# CPU.net
KiCad netlist of a schematic drawn in Altium Designer
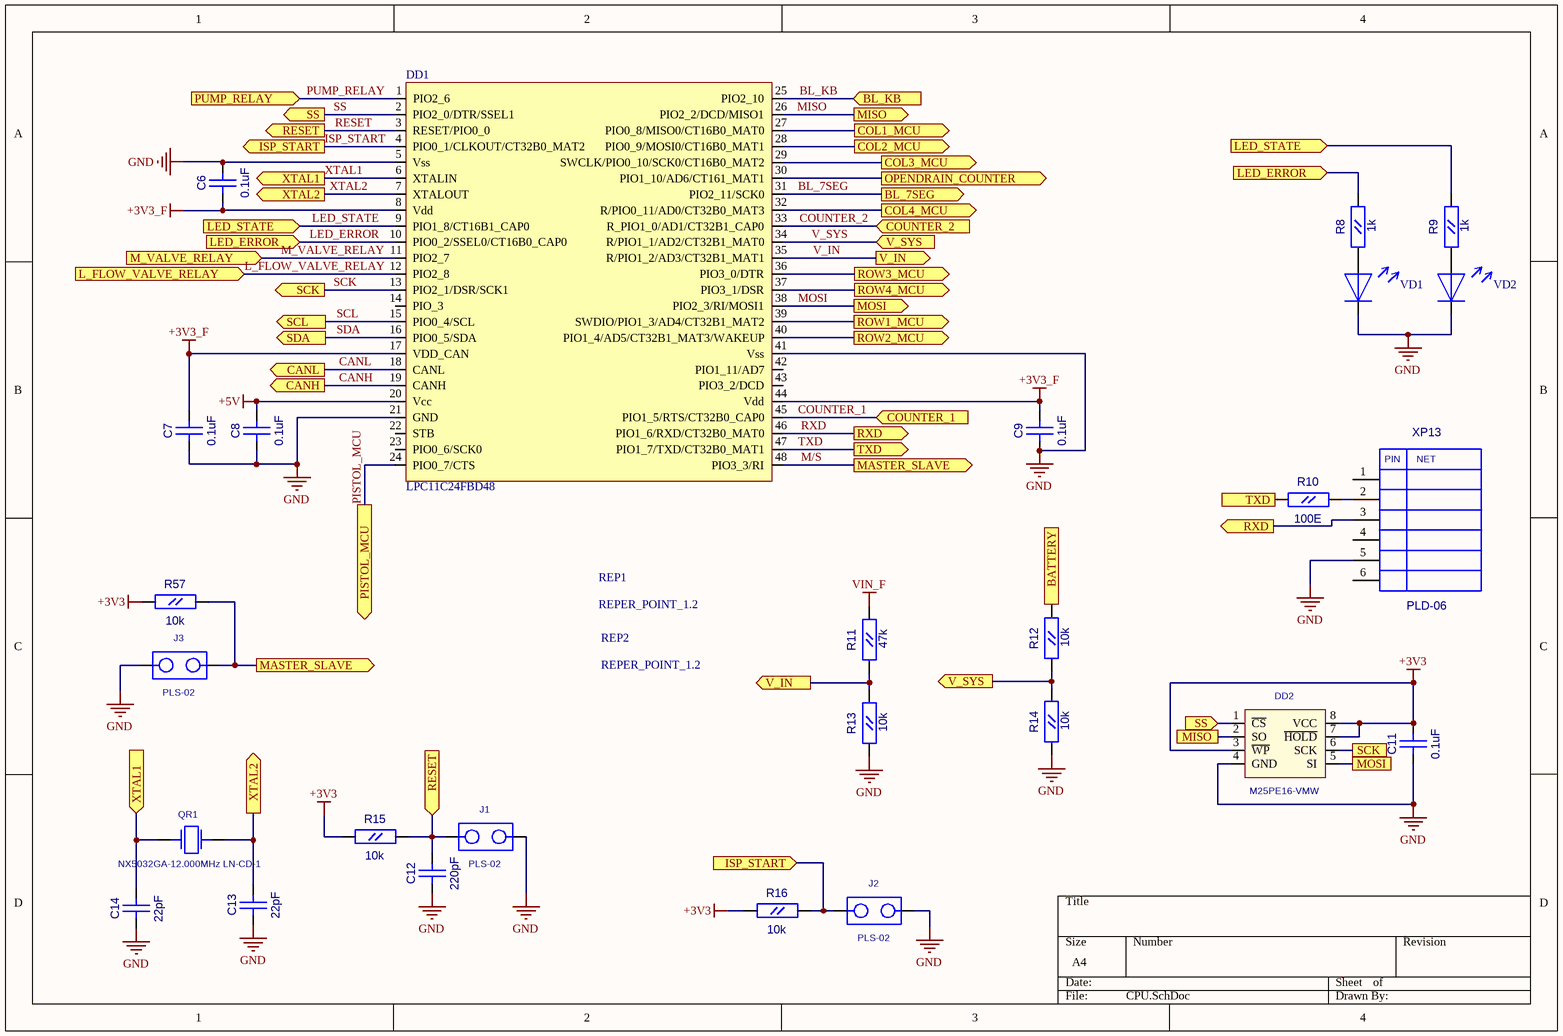
[diagram p0: CPU.SchDoc]

(export (version "E")
  (design (tool "Eeschema 10.0.6"))
  (components
    (comp (ref "C6")
      (value "0.1uF")
      (footprint "CC0603")
      (description "CC0603")
      (libsource (lib "gprs_modem_2") (part "CC0603"))
    )
    (comp (ref "C7")
      (value "0.1uF")
      (footprint "CC0603")
      (description "CC0603")
      (libsource (lib "gprs_modem_2") (part "CC0603"))
    )
    (comp (ref "C8")
      (value "0.1uF")
      (footprint "CC0603")
      (description "CC0603")
      (libsource (lib "gprs_modem_2") (part "CC0603"))
    )
    (comp (ref "C9")
      (value "0.1uF")
      (footprint "CC0603")
      (description "CC0603")
      (libsource (lib "gprs_modem_2") (part "CC0603"))
    )
    (comp (ref "C11")
      (value "0.1uF")
      (footprint "CC0603")
      (description "CC0603")
      (libsource (lib "gprs_modem_2") (part "CC0603"))
    )
    (comp (ref "C12")
      (value "220pF")
      (footprint "CC0603")
      (description "CC0603")
      (libsource (lib "gprs_modem_2") (part "CC0603"))
    )
    (comp (ref "C13")
      (value "22pF")
      (footprint "CC0603")
      (description "CC0603")
      (libsource (lib "gprs_modem_2") (part "CC0603"))
    )
    (comp (ref "C14")
      (value "22pF")
      (footprint "CC0603")
      (description "CC0603")
      (libsource (lib "gprs_modem_2") (part "CC0603"))
    )
    (comp (ref "DD1")
      (value "LPC11C24FBD48")
      (footprint "LQFP48")
      (libsource (lib "gprs_modem_2") (part "LPC11C24FBD48"))
    )
    (comp (ref "DD2")
      (value "M25PE16-VMW")
      (footprint "EIAJ_SO8")
      (description "S25FL016A0LMFI01")
      (libsource (lib "gprs_modem_2") (part "S25FL016A0LMFI01"))
    )
    (comp (ref "J1") (value "PLS-02") (footprint "PLS-02") (libsource (lib "gprs_modem_2") (part "PLS-02")))
    (comp (ref "J2") (value "PLS-02") (footprint "PLS-02") (libsource (lib "gprs_modem_2") (part "PLS-02")))
    (comp (ref "J3") (value "PLS-02") (footprint "PLS-02") (libsource (lib "gprs_modem_2") (part "PLS-02")))
    (comp (ref "QR1")
      (value "NX5032GA-12.000MHz LN-CD-1")
      (footprint "AC5032_2")
      (description "AC5032/2")
      (libsource (lib "gprs_modem_2") (part "AC5032_2"))
    )
    (comp (ref "R8")
      (value "1k")
      (footprint "RC0603")
      (description "RC0603")
      (libsource (lib "gprs_modem_2") (part "RC0603"))
    )
    (comp (ref "R9")
      (value "1k")
      (footprint "RC0603")
      (description "RC0603")
      (libsource (lib "gprs_modem_2") (part "RC0603"))
    )
    (comp (ref "R10")
      (value "100E")
      (footprint "RC0603")
      (description "RC0603")
      (libsource (lib "gprs_modem_2") (part "RC0603"))
    )
    (comp (ref "R11")
      (value "47k")
      (footprint "RC0603")
      (description "RC0603")
      (libsource (lib "gprs_modem_2") (part "RC0603"))
    )
    (comp (ref "R12")
      (value "10k")
      (footprint "RC0603")
      (description "RC0603")
      (libsource (lib "gprs_modem_2") (part "RC0603"))
    )
    (comp (ref "R13")
      (value "10k")
      (footprint "RC0603")
      (description "RC0603")
      (libsource (lib "gprs_modem_2") (part "RC0603"))
    )
    (comp (ref "R14")
      (value "10k")
      (footprint "RC0603")
      (description "RC0603")
      (libsource (lib "gprs_modem_2") (part "RC0603"))
    )
    (comp (ref "R15")
      (value "10k")
      (footprint "RC0603")
      (description "RC0603")
      (libsource (lib "gprs_modem_2") (part "RC0603"))
    )
    (comp (ref "R16")
      (value "10k")
      (footprint "RC0603")
      (description "RC0603")
      (libsource (lib "gprs_modem_2") (part "RC0603"))
    )
    (comp (ref "R57")
      (value "10k")
      (footprint "RC0603")
      (description "RC0603")
      (libsource (lib "gprs_modem_2") (part "RC0603"))
    )
    (comp (ref "REP1")
      (value "REPER_POINT_1.2")
      (footprint "REPER1.2")
      (description "REPER1.2")
      (libsource (lib "gprs_modem_2") (part "REPER1.2"))
    )
    (comp (ref "REP2")
      (value "REPER_POINT_1.2")
      (footprint "REPER1.2")
      (description "REPER1.2")
      (libsource (lib "gprs_modem_2") (part "REPER1.2"))
    )
    (comp (ref "VD1")
      (value "LED_0805")
      (footprint "LED0805")
      (libsource (lib "gprs_modem_2") (part "LED_0805"))
    )
    (comp (ref "VD2")
      (value "LED_0805")
      (footprint "LED0805")
      (libsource (lib "gprs_modem_2") (part "LED_0805"))
    )
    (comp (ref "XP13")
      (value "PLD-06")
      (footprint "PIN6")
      (description "PLD06")
      (libsource (lib "gprs_modem_2") (part "PLD-06"))
    )
  )
  (nets
    (net (code "1") (name "+3V3") (class "Default")
      (node (ref "C11") (pin "2") (pinfunction "B_2") (pintype "passive"))
      (node (ref "DD2") (pin "3") (pinfunction "~{WP}_3") (pintype "passive"))
      (node (ref "DD2") (pin "7") (pinfunction "~{HOLD}_7") (pintype "passive"))
      (node (ref "DD2") (pin "8") (pinfunction "VCC_8") (pintype "passive"))
      (node (ref "R15") (pin "1") (pinfunction "A_1") (pintype "passive"))
      (node (ref "R16") (pin "1") (pinfunction "A_1") (pintype "passive"))
      (node (ref "R57") (pin "1") (pinfunction "A_1") (pintype "passive"))
    )
    (net (code "2") (name "+3V3_F") (class "Default")
      (node (ref "C6") (pin "1") (pinfunction "A_1") (pintype "passive"))
      (node (ref "C7") (pin "2") (pinfunction "B_2") (pintype "passive"))
      (node (ref "C9") (pin "2") (pinfunction "B_2") (pintype "passive"))
      (node (ref "DD1") (pin "17") (pinfunction "VDD_CAN_17") (pintype "passive"))
      (node (ref "DD1") (pin "44") (pinfunction "Vdd_44") (pintype "passive"))
      (node (ref "DD1") (pin "8") (pinfunction "Vdd_8") (pintype "passive"))
    )
    (net (code "3") (name "+5V") (class "Default")
      (node (ref "C8") (pin "2") (pinfunction "B_2") (pintype "passive"))
      (node (ref "DD1") (pin "20") (pinfunction "Vcc_20") (pintype "passive"))
    )
    (net (code "4") (name "/BATTERY") (class "Default")
      (node (ref "R12") (pin "2") (pinfunction "B_2") (pintype "passive"))
    )
    (net (code "5") (name "/BL_7SEG") (class "Default")
      (node (ref "DD1") (pin "31") (pinfunction "PIO2_11/SCK0_31") (pintype "passive"))
    )
    (net (code "6") (name "/BL_KB") (class "Default")
      (node (ref "DD1") (pin "25") (pinfunction "PIO2_10_25") (pintype "passive"))
    )
    (net (code "7") (name "/CANH") (class "Default")
      (node (ref "DD1") (pin "19") (pinfunction "CANH_19") (pintype "passive"))
    )
    (net (code "8") (name "/CANL") (class "Default")
      (node (ref "DD1") (pin "18") (pinfunction "CANL_18") (pintype "passive"))
    )
    (net (code "9") (name "/COL1_MCU") (class "Default")
      (node (ref "DD1") (pin "27") (pinfunction "PIO0_8/MISO0/CT16B0_MAT0_27") (pintype "passive"))
    )
    (net (code "10") (name "/COL2_MCU") (class "Default")
      (node (ref "DD1") (pin "28") (pinfunction "PIO0_9/MOSI0/CT16B0_MAT1_28") (pintype "passive"))
    )
    (net (code "11") (name "/COL3_MCU") (class "Default")
      (node (ref "DD1") (pin "29") (pinfunction "SWCLK/PIO0_10/SCK0/CT16B0_MAT2_29") (pintype "passive"))
    )
    (net (code "12") (name "/COL4_MCU") (class "Default")
      (node (ref "DD1") (pin "32") (pinfunction "R/PIO0_11/AD0/CT32B0_MAT3_32") (pintype "passive"))
    )
    (net (code "13") (name "/COUNTER_1") (class "Default")
      (node (ref "DD1") (pin "45") (pinfunction "PIO1_5/RTS/CT32B0_CAP0_45") (pintype "passive"))
    )
    (net (code "14") (name "/COUNTER_2") (class "Default")
      (node (ref "DD1") (pin "33") (pinfunction "R_PIO1_0/AD1/CT32B1_CAP0_33") (pintype "passive"))
    )
    (net (code "15") (name "/ISP_START") (class "Default")
      (node (ref "DD1") (pin "4") (pinfunction "PIO0_1/CLKOUT/CT32B0_MAT2_4") (pintype "passive"))
      (node (ref "J2") (pin "1") (pintype "passive"))
      (node (ref "R16") (pin "2") (pinfunction "B_2") (pintype "passive"))
    )
    (net (code "16") (name "/LED_ERROR") (class "Default")
      (node (ref "DD1") (pin "10") (pinfunction "PIO0_2/SSEL0/CT16B0_CAP0_10") (pintype "passive"))
      (node (ref "R8") (pin "2") (pinfunction "B_2") (pintype "passive"))
    )
    (net (code "17") (name "/LED_STATE") (class "Default")
      (node (ref "DD1") (pin "9") (pinfunction "PIO1_8/CT16B1_CAP0_9") (pintype "passive"))
      (node (ref "R9") (pin "2") (pinfunction "B_2") (pintype "passive"))
    )
    (net (code "18") (name "/L_FLOW_VALVE_RELAY") (class "Default")
      (node (ref "DD1") (pin "12") (pinfunction "PIO2_8_12") (pintype "passive"))
    )
    (net (code "19") (name "/MISO") (class "Default")
      (node (ref "DD1") (pin "26") (pinfunction "PIO2_2/DCD/MISO1_26") (pintype "passive"))
      (node (ref "DD2") (pin "2") (pinfunction "SO_2") (pintype "passive"))
    )
    (net (code "20") (name "/MOSI") (class "Default")
      (node (ref "DD1") (pin "38") (pinfunction "PIO2_3/RI/MOSI1_38") (pintype "passive"))
      (node (ref "DD2") (pin "5") (pinfunction "SI_5") (pintype "passive"))
    )
    (net (code "21") (name "/M_VALVE_RELAY") (class "Default")
      (node (ref "DD1") (pin "11") (pinfunction "PIO2_7_11") (pintype "passive"))
    )
    (net (code "22") (name "/M{slash}S") (class "Default")
      (node (ref "DD1") (pin "48") (pinfunction "PIO3_3/RI_48") (pintype "passive"))
      (node (ref "J3") (pin "2") (pintype "passive"))
      (node (ref "R57") (pin "2") (pinfunction "B_2") (pintype "passive"))
    )
    (net (code "23") (name "/OPENDRAIN_COUNTER") (class "Default")
      (node (ref "DD1") (pin "30") (pinfunction "PIO1_10/AD6/CT161_MAT1_30") (pintype "passive"))
    )
    (net (code "24") (name "/PISTOL_MCU") (class "Default")
      (node (ref "DD1") (pin "24") (pinfunction "PIO0_7/CTS_24") (pintype "passive"))
    )
    (net (code "25") (name "/PUMP_RELAY") (class "Default")
      (node (ref "DD1") (pin "1") (pinfunction "PIO2_6_1") (pintype "passive"))
    )
    (net (code "26") (name "/RESET") (class "Default")
      (node (ref "C12") (pin "2") (pinfunction "B_2") (pintype "passive"))
      (node (ref "DD1") (pin "3") (pinfunction "RESET/PIO0_0_3") (pintype "passive"))
      (node (ref "J1") (pin "1") (pintype "passive"))
      (node (ref "R15") (pin "2") (pinfunction "B_2") (pintype "passive"))
    )
    (net (code "27") (name "/ROW1_MCU") (class "Default")
      (node (ref "DD1") (pin "39") (pinfunction "SWDIO/PIO1_3/AD4/CT32B1_MAT2_39") (pintype "passive"))
    )
    (net (code "28") (name "/ROW2_MCU") (class "Default")
      (node (ref "DD1") (pin "40") (pinfunction "PIO1_4/AD5/CT32B1_MAT3/WAKEUP_40") (pintype "passive"))
    )
    (net (code "29") (name "/ROW3_MCU") (class "Default")
      (node (ref "DD1") (pin "36") (pinfunction "PIO3_0/DTR_36") (pintype "passive"))
    )
    (net (code "30") (name "/ROW4_MCU") (class "Default")
      (node (ref "DD1") (pin "37") (pinfunction "PIO3_1/DSR_37") (pintype "passive"))
    )
    (net (code "31") (name "/RXD") (class "Default")
      (node (ref "DD1") (pin "46") (pinfunction "PIO1_6/RXD/CT32B0_MAT0_46") (pintype "passive"))
      (node (ref "XP13") (pin "3") (pinfunction "3_3") (pintype "passive"))
    )
    (net (code "32") (name "/SCK") (class "Default")
      (node (ref "DD1") (pin "13") (pinfunction "PIO2_1/DSR/SCK1_13") (pintype "passive"))
      (node (ref "DD2") (pin "6") (pinfunction "SCK_6") (pintype "passive"))
    )
    (net (code "33") (name "/SCL") (class "Default")
      (node (ref "DD1") (pin "15") (pinfunction "PIO0_4/SCL_15") (pintype "passive"))
    )
    (net (code "34") (name "/SDA") (class "Default")
      (node (ref "DD1") (pin "16") (pinfunction "PIO0_5/SDA_16") (pintype "passive"))
    )
    (net (code "35") (name "/SS") (class "Default")
      (node (ref "DD1") (pin "2") (pinfunction "PIO2_0/DTR/SSEL1_2") (pintype "passive"))
      (node (ref "DD2") (pin "1") (pinfunction "~{CS}_1") (pintype "passive"))
    )
    (net (code "36") (name "/TXD") (class "Default")
      (node (ref "DD1") (pin "47") (pinfunction "PIO1_7/TXD/CT32B0_MAT1_47") (pintype "passive"))
      (node (ref "R10") (pin "1") (pinfunction "A_1") (pintype "passive"))
    )
    (net (code "37") (name "/V_IN") (class "Default")
      (node (ref "DD1") (pin "35") (pinfunction "R/PIO1_2/AD3/CT32B1_MAT1_35") (pintype "passive"))
      (node (ref "R11") (pin "1") (pinfunction "A_1") (pintype "passive"))
      (node (ref "R13") (pin "2") (pinfunction "B_2") (pintype "passive"))
    )
    (net (code "38") (name "/V_SYS") (class "Default")
      (node (ref "DD1") (pin "34") (pinfunction "R/PIO1_1/AD2/CT32B1_MAT0_34") (pintype "passive"))
      (node (ref "R12") (pin "1") (pinfunction "A_1") (pintype "passive"))
      (node (ref "R14") (pin "2") (pinfunction "B_2") (pintype "passive"))
    )
    (net (code "39") (name "/XTAL1") (class "Default")
      (node (ref "C14") (pin "2") (pinfunction "B_2") (pintype "passive"))
      (node (ref "DD1") (pin "6") (pinfunction "XTALIN_6") (pintype "passive"))
      (node (ref "QR1") (pin "1") (pintype "passive"))
    )
    (net (code "40") (name "/XTAL2") (class "Default")
      (node (ref "C13") (pin "2") (pinfunction "B_2") (pintype "passive"))
      (node (ref "DD1") (pin "7") (pinfunction "XTALOUT_7") (pintype "passive"))
      (node (ref "QR1") (pin "2") (pintype "passive"))
    )
    (net (code "41") (name "GND") (class "Default")
      (node (ref "C11") (pin "1") (pinfunction "A_1") (pintype "passive"))
      (node (ref "C12") (pin "1") (pinfunction "A_1") (pintype "passive"))
      (node (ref "C13") (pin "1") (pinfunction "A_1") (pintype "passive"))
      (node (ref "C14") (pin "1") (pinfunction "A_1") (pintype "passive"))
      (node (ref "C6") (pin "2") (pinfunction "B_2") (pintype "passive"))
      (node (ref "C7") (pin "1") (pinfunction "A_1") (pintype "passive"))
      (node (ref "C8") (pin "1") (pinfunction "A_1") (pintype "passive"))
      (node (ref "C9") (pin "1") (pinfunction "A_1") (pintype "passive"))
      (node (ref "DD1") (pin "21") (pinfunction "GND_21") (pintype "passive"))
      (node (ref "DD1") (pin "41") (pinfunction "Vss_41") (pintype "passive"))
      (node (ref "DD1") (pin "5") (pinfunction "Vss_5") (pintype "passive"))
      (node (ref "DD2") (pin "4") (pinfunction "GND_4") (pintype "passive"))
      (node (ref "J1") (pin "2") (pintype "passive"))
      (node (ref "J2") (pin "2") (pintype "passive"))
      (node (ref "J3") (pin "1") (pintype "passive"))
      (node (ref "R13") (pin "1") (pinfunction "A_1") (pintype "passive"))
      (node (ref "R14") (pin "1") (pinfunction "A_1") (pintype "passive"))
      (node (ref "VD1") (pin "2") (pintype "passive"))
      (node (ref "VD2") (pin "2") (pintype "passive"))
      (node (ref "XP13") (pin "5") (pinfunction "5_5") (pintype "passive"))
    )
    (net (code "42") (name "Net-(R8-A)") (class "Default")
      (node (ref "R8") (pin "1") (pinfunction "A_1") (pintype "passive"))
      (node (ref "VD1") (pin "1") (pintype "passive"))
    )
    (net (code "43") (name "Net-(R9-A)") (class "Default")
      (node (ref "R9") (pin "1") (pinfunction "A_1") (pintype "passive"))
      (node (ref "VD2") (pin "1") (pintype "passive"))
    )
    (net (code "44") (name "Net-(R10-B)") (class "Default")
      (node (ref "R10") (pin "2") (pinfunction "B_2") (pintype "passive"))
      (node (ref "XP13") (pin "2") (pinfunction "2_2") (pintype "passive"))
    )
    (net (code "45") (name "VIN_F") (class "Default")
      (node (ref "R11") (pin "2") (pinfunction "B_2") (pintype "passive"))
    )
    (net (code "46") (name "unconnected-(DD1-PIO0_6{slash}SCK0-Pad23)") (class "Default")
      (node (ref "DD1") (pin "23") (pinfunction "PIO0_6/SCK0_23") (pintype "passive"))
    )
    (net (code "47") (name "unconnected-(DD1-PIO1_11{slash}AD7-Pad42)") (class "Default")
      (node (ref "DD1") (pin "42") (pinfunction "PIO1_11/AD7_42") (pintype "passive"))
    )
    (net (code "48") (name "unconnected-(DD1-PIO3_2{slash}DCD-Pad43)") (class "Default")
      (node (ref "DD1") (pin "43") (pinfunction "PIO3_2/DCD_43") (pintype "passive"))
    )
    (net (code "49") (name "unconnected-(DD1-PIO_3-Pad14)") (class "Default")
      (node (ref "DD1") (pin "14") (pinfunction "PIO_3_14") (pintype "passive"))
    )
    (net (code "50") (name "unconnected-(DD1-STB-Pad22)") (class "Default")
      (node (ref "DD1") (pin "22") (pinfunction "STB_22") (pintype "passive"))
    )
    (net (code "51") (name "unconnected-(REP1-Pad1)") (class "Default")
      (node (ref "REP1") (pin "1") (pintype "passive"))
    )
    (net (code "52") (name "unconnected-(REP2-Pad1)") (class "Default")
      (node (ref "REP2") (pin "1") (pintype "passive"))
    )
    (net (code "53") (name "unconnected-(XP13-Pad1)") (class "Default")
      (node (ref "XP13") (pin "1") (pinfunction "1_1") (pintype "passive"))
    )
    (net (code "54") (name "unconnected-(XP13-Pad4)") (class "Default")
      (node (ref "XP13") (pin "4") (pinfunction "4_4") (pintype "passive"))
    )
    (net (code "55") (name "unconnected-(XP13-Pad6)") (class "Default")
      (node (ref "XP13") (pin "6") (pinfunction "6_6") (pintype "passive"))
    )
  )
)
